# PWM_OUT.net
KiCad netlist of a schematic drawn in Altium Designer
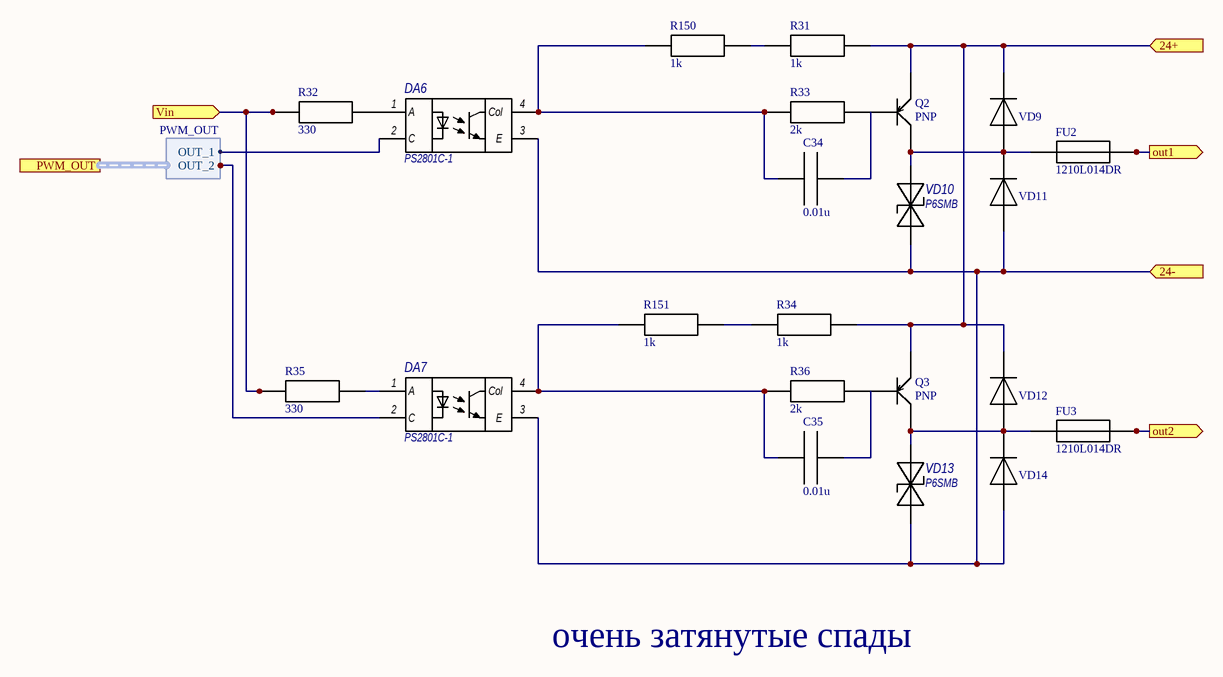
[diagram p0: PWM_OUT.SchDoc]

(export (version "E")
  (design (tool "Eeschema 10.0.6"))
  (components
    (comp (ref "C34") (value "0.01u") (footprint "cap_0402") (libsource (lib "lib") (part "cap")))
    (comp (ref "C35") (value "0.01u") (footprint "cap_0402") (libsource (lib "lib") (part "cap")))
    (comp (ref "DA6")
      (value "PS2801C-1")
      (footprint "SSOP-4N")
      (fields (field (name "TYPE") "PS2801C-1"))
      (libsource (lib "Optocoupler") (part "PS2801C-1"))
    )
    (comp (ref "DA7")
      (value "PS2801C-1")
      (footprint "SSOP-4N")
      (fields (field (name "TYPE") "PS2801C-1"))
      (libsource (lib "Optocoupler") (part "PS2801C-1"))
    )
    (comp (ref "FU2") (value "1210L014DR") (footprint "fuse1210") (libsource (lib "lib") (part "fuse")))
    (comp (ref "FU3") (value "1210L014DR") (footprint "fuse1210") (libsource (lib "lib") (part "fuse")))
    (comp (ref "Q2") (value "PNP") (footprint "sot23") (libsource (lib "lib") (part "PNP")))
    (comp (ref "Q3") (value "PNP") (footprint "sot23") (libsource (lib "lib") (part "PNP")))
    (comp (ref "R31") (value "1k") (footprint "Lib:0805-res") (libsource (lib "lib") (part "res")))
    (comp (ref "R32") (value "330") (footprint "res_0402") (libsource (lib "lib") (part "res")))
    (comp (ref "R33") (value "2k") (footprint "res_0402") (libsource (lib "lib") (part "res")))
    (comp (ref "R34") (value "1k") (footprint "Lib:0805-res") (libsource (lib "lib") (part "res")))
    (comp (ref "R35") (value "330") (footprint "res_0402") (libsource (lib "lib") (part "res")))
    (comp (ref "R36") (value "2k") (footprint "res_0402") (libsource (lib "lib") (part "res")))
    (comp (ref "R150") (value "1k") (footprint "Lib:0805-res") (libsource (lib "lib") (part "res")))
    (comp (ref "R151") (value "1k") (footprint "Lib:0805-res") (libsource (lib "lib") (part "res")))
    (comp (ref "VD9") (value "1N4448") (footprint "sod-323") (libsource (lib "lib") (part "1N4448")))
    (comp (ref "VD10")
      (value "PTVS33VS1UTR")
      (footprint "SOD-123")
      (description "PTVS33VS1UTR,115, TVS DIODE 33VWM 53.3VC SOD123W")
      (fields (field (name "TYPE") "P6SMB"))
      (libsource (lib "lib") (part "PTVS33VS1UTR"))
    )
    (comp (ref "VD11") (value "1N4448") (footprint "sod-323") (libsource (lib "lib") (part "1N4448")))
    (comp (ref "VD12") (value "1N4448") (footprint "sod-323") (libsource (lib "lib") (part "1N4448")))
    (comp (ref "VD13")
      (value "PTVS33VS1UTR")
      (footprint "SOD-123")
      (description "PTVS33VS1UTR,115, TVS DIODE 33VWM 53.3VC SOD123W")
      (fields (field (name "TYPE") "P6SMB"))
      (libsource (lib "lib") (part "PTVS33VS1UTR"))
    )
    (comp (ref "VD14") (value "1N4448") (footprint "sod-323") (libsource (lib "lib") (part "1N4448")))
  )
  (nets
    (net (code "2") (name "/24+") (class "Default")
      (node (ref "Q2") (pin "3") (pinfunction "K_3") (pintype "passive"))
      (node (ref "Q3") (pin "3") (pinfunction "K_3") (pintype "passive"))
      (node (ref "R31") (pin "2") (pinfunction "2_2") (pintype "passive"))
      (node (ref "R34") (pin "2") (pinfunction "2_2") (pintype "passive"))
      (node (ref "VD12") (pin "K") (pinfunction "K_K") (pintype "passive"))
      (node (ref "VD9") (pin "K") (pinfunction "K_K") (pintype "passive"))
    )
    (net (code "3") (name "/24-") (class "Default")
      (node (ref "DA6") (pin "3") (pinfunction "E_3") (pintype "passive"))
      (node (ref "DA7") (pin "3") (pinfunction "E_3") (pintype "passive"))
      (node (ref "VD10") (pin "A") (pinfunction "A_A") (pintype "passive"))
      (node (ref "VD11") (pin "A") (pinfunction "A_A") (pintype "passive"))
      (node (ref "VD13") (pin "A") (pinfunction "A_A") (pintype "passive"))
      (node (ref "VD14") (pin "A") (pinfunction "A_A") (pintype "passive"))
    )
    (net (code "4") (name "/OUT_1") (class "Default")
      (node (ref "DA6") (pin "2") (pinfunction "C_2") (pintype "passive"))
    )
    (net (code "5") (name "/OUT_2") (class "Default")
      (node (ref "DA7") (pin "2") (pinfunction "C_2") (pintype "passive"))
    )
    (net (code "6") (name "/Vin") (class "Default")
      (node (ref "R32") (pin "1") (pinfunction "1_1") (pintype "passive"))
      (node (ref "R35") (pin "1") (pinfunction "1_1") (pintype "passive"))
    )
    (net (code "7") (name "/out1") (class "Default")
      (node (ref "FU2") (pin "2") (pinfunction "2_2") (pintype "passive"))
    )
    (net (code "8") (name "/out2") (class "Default")
      (node (ref "FU3") (pin "2") (pinfunction "2_2") (pintype "passive"))
    )
    (net (code "10") (name "Net-(DA6-A)") (class "Default")
      (node (ref "DA6") (pin "1") (pinfunction "A_1") (pintype "passive"))
      (node (ref "R32") (pin "2") (pinfunction "2_2") (pintype "passive"))
    )
    (net (code "11") (name "Net-(DA6-Col)") (class "Default")
      (node (ref "C34") (pin "1") (pinfunction "1_1") (pintype "passive"))
      (node (ref "DA6") (pin "4") (pinfunction "Col_4") (pintype "passive"))
      (node (ref "R150") (pin "1") (pinfunction "1_1") (pintype "passive"))
      (node (ref "R33") (pin "1") (pinfunction "1_1") (pintype "passive"))
    )
    (net (code "12") (name "Net-(DA7-A)") (class "Default")
      (node (ref "DA7") (pin "1") (pinfunction "A_1") (pintype "passive"))
      (node (ref "R35") (pin "2") (pinfunction "2_2") (pintype "passive"))
    )
    (net (code "13") (name "Net-(DA7-Col)") (class "Default")
      (node (ref "C35") (pin "1") (pinfunction "1_1") (pintype "passive"))
      (node (ref "DA7") (pin "4") (pinfunction "Col_4") (pintype "passive"))
      (node (ref "R151") (pin "1") (pinfunction "1_1") (pintype "passive"))
      (node (ref "R36") (pin "1") (pinfunction "1_1") (pintype "passive"))
    )
    (net (code "14") (name "Net-(Q2-B)") (class "Default")
      (node (ref "C34") (pin "2") (pinfunction "2_2") (pintype "passive"))
      (node (ref "Q2") (pin "1") (pinfunction "B_1") (pintype "passive"))
      (node (ref "R33") (pin "2") (pinfunction "2_2") (pintype "passive"))
    )
    (net (code "15") (name "Net-(Q2-E)") (class "Default")
      (node (ref "FU2") (pin "1") (pinfunction "1_1") (pintype "passive"))
      (node (ref "Q2") (pin "2") (pinfunction "E_2") (pintype "passive"))
      (node (ref "VD10") (pin "K") (pinfunction "K_K") (pintype "passive"))
      (node (ref "VD11") (pin "K") (pinfunction "K_K") (pintype "passive"))
      (node (ref "VD9") (pin "A") (pinfunction "A_A") (pintype "passive"))
    )
    (net (code "16") (name "Net-(Q3-B)") (class "Default")
      (node (ref "C35") (pin "2") (pinfunction "2_2") (pintype "passive"))
      (node (ref "Q3") (pin "1") (pinfunction "B_1") (pintype "passive"))
      (node (ref "R36") (pin "2") (pinfunction "2_2") (pintype "passive"))
    )
    (net (code "17") (name "Net-(Q3-E)") (class "Default")
      (node (ref "FU3") (pin "1") (pinfunction "1_1") (pintype "passive"))
      (node (ref "Q3") (pin "2") (pinfunction "E_2") (pintype "passive"))
      (node (ref "VD12") (pin "A") (pinfunction "A_A") (pintype "passive"))
      (node (ref "VD13") (pin "K") (pinfunction "K_K") (pintype "passive"))
      (node (ref "VD14") (pin "K") (pinfunction "K_K") (pintype "passive"))
    )
    (net (code "18") (name "Net-(R150-Pad2)") (class "Default")
      (node (ref "R150") (pin "2") (pinfunction "2_2") (pintype "passive"))
      (node (ref "R31") (pin "1") (pinfunction "1_1") (pintype "passive"))
    )
    (net (code "19") (name "Net-(R151-Pad2)") (class "Default")
      (node (ref "R151") (pin "2") (pinfunction "2_2") (pintype "passive"))
      (node (ref "R34") (pin "1") (pinfunction "1_1") (pintype "passive"))
    )
  )
)
